# PIC18F4520_2.net
KiCad netlist of a schematic drawn in EAGLE
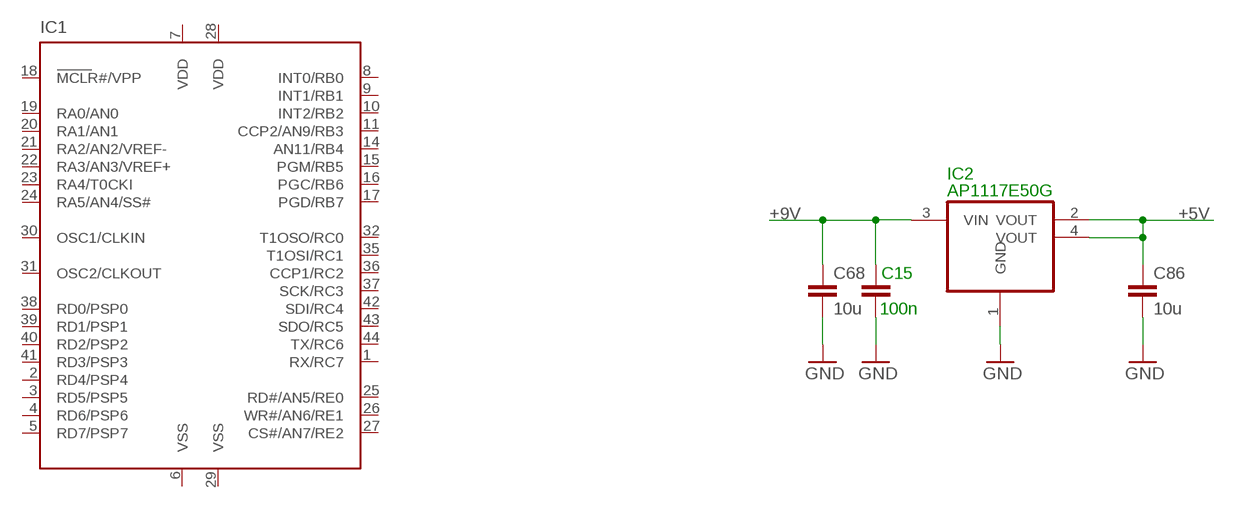
[diagram p0: schematic, sheet 1]

(export (version "E")
  (design (tool "Eeschema 10.0.6"))
  (components
    (comp (ref "C15")
      (value "100n")
      (footprint "eagle-import:C0805")
      (libsource (lib "eagle-import") (part "rcl_416_C-EUC0805"))
    )
    (comp (ref "C68")
      (value "10u")
      (footprint "eagle-import:C0805")
      (libsource (lib "eagle-import") (part "C-EUC0805"))
    )
    (comp (ref "C86")
      (value "10u")
      (footprint "eagle-import:C0805")
      (libsource (lib "eagle-import") (part "C-EUC0805"))
    )
    (comp (ref "IC1")
      (value "PIC18F4520")
      (footprint "eagle-import:TQFP44")
      (libsource (lib "eagle-import") (part "PIC18F4520"))
    )
    (comp (ref "IC2")
      (value "AP1117E50G")
      (footprint "eagle-import:SOT223")
      (libsource (lib "eagle-import") (part "REG1117-2OUT"))
    )
  )
  (nets
    (net (code "1") (name "/+5V") (class "Default")
      (node (ref "C86") (pin "1") (pinfunction "1_1") (pintype "passive"))
      (node (ref "IC2") (pin "2") (pinfunction "VOUT_2") (pintype "output"))
      (node (ref "IC2") (pin "4") (pinfunction "VOUT_4") (pintype "bidirectional"))
    )
    (net (code "2") (name "/+9V") (class "Default")
      (node (ref "C15") (pin "1") (pinfunction "1_1") (pintype "passive"))
      (node (ref "C68") (pin "1") (pinfunction "1_1") (pintype "passive"))
      (node (ref "IC2") (pin "3") (pinfunction "VIN_3") (pintype "input"))
    )
    (net (code "3") (name "GND") (class "Default")
      (node (ref "C15") (pin "2") (pinfunction "2_2") (pintype "passive"))
      (node (ref "C68") (pin "2") (pinfunction "2_2") (pintype "passive"))
      (node (ref "C86") (pin "2") (pinfunction "2_2") (pintype "passive"))
      (node (ref "IC2") (pin "1") (pinfunction "GND_1") (pintype "power_in"))
    )
    (net (code "4") (name "unconnected-(IC1-AN11{slash}RB4-Pad14)") (class "Default")
      (node (ref "IC1") (pin "14") (pinfunction "AN11/RB4_14") (pintype "bidirectional"))
    )
    (net (code "5") (name "unconnected-(IC1-CCP1{slash}RC2-Pad36)") (class "Default")
      (node (ref "IC1") (pin "36") (pinfunction "CCP1/RC2_36") (pintype "bidirectional"))
    )
    (net (code "6") (name "unconnected-(IC1-CCP2{slash}AN9{slash}RB3-Pad11)") (class "Default")
      (node (ref "IC1") (pin "11") (pinfunction "CCP2/AN9/RB3_11") (pintype "bidirectional"))
    )
    (net (code "7") (name "unconnected-(IC1-CS#{slash}AN7{slash}RE2-Pad27)") (class "Default")
      (node (ref "IC1") (pin "27") (pinfunction "CS#/AN7/RE2_27") (pintype "bidirectional"))
    )
    (net (code "8") (name "unconnected-(IC1-INT0{slash}RB0-Pad8)") (class "Default")
      (node (ref "IC1") (pin "8") (pinfunction "INT0/RB0_8") (pintype "bidirectional"))
    )
    (net (code "9") (name "unconnected-(IC1-INT1{slash}RB1-Pad9)") (class "Default")
      (node (ref "IC1") (pin "9") (pinfunction "INT1/RB1_9") (pintype "bidirectional"))
    )
    (net (code "10") (name "unconnected-(IC1-INT2{slash}RB2-Pad10)") (class "Default")
      (node (ref "IC1") (pin "10") (pinfunction "INT2/RB2_10") (pintype "bidirectional"))
    )
    (net (code "11") (name "unconnected-(IC1-MCLR#{slash}VPP-Pad18)") (class "Default")
      (node (ref "IC1") (pin "18") (pinfunction "MCLR#/VPP_18") (pintype "input"))
    )
    (net (code "12") (name "unconnected-(IC1-OSC1{slash}CLKIN-Pad30)") (class "Default")
      (node (ref "IC1") (pin "30") (pinfunction "OSC1/CLKIN_30") (pintype "input"))
    )
    (net (code "13") (name "unconnected-(IC1-OSC2{slash}CLKOUT-Pad31)") (class "Default")
      (node (ref "IC1") (pin "31") (pinfunction "OSC2/CLKOUT_31") (pintype "output"))
    )
    (net (code "14") (name "unconnected-(IC1-PGC{slash}RB6-Pad16)") (class "Default")
      (node (ref "IC1") (pin "16") (pinfunction "PGC/RB6_16") (pintype "bidirectional"))
    )
    (net (code "15") (name "unconnected-(IC1-PGD{slash}RB7-Pad17)") (class "Default")
      (node (ref "IC1") (pin "17") (pinfunction "PGD/RB7_17") (pintype "bidirectional"))
    )
    (net (code "16") (name "unconnected-(IC1-PGM{slash}RB5-Pad15)") (class "Default")
      (node (ref "IC1") (pin "15") (pinfunction "PGM/RB5_15") (pintype "bidirectional"))
    )
    (net (code "17") (name "unconnected-(IC1-RA0{slash}AN0-Pad19)") (class "Default")
      (node (ref "IC1") (pin "19") (pinfunction "RA0/AN0_19") (pintype "bidirectional"))
    )
    (net (code "18") (name "unconnected-(IC1-RA1{slash}AN1-Pad20)") (class "Default")
      (node (ref "IC1") (pin "20") (pinfunction "RA1/AN1_20") (pintype "bidirectional"))
    )
    (net (code "19") (name "unconnected-(IC1-RA2{slash}AN2{slash}VREF--Pad21)") (class "Default")
      (node (ref "IC1") (pin "21") (pinfunction "RA2/AN2/VREF-_21") (pintype "bidirectional"))
    )
    (net (code "20") (name "unconnected-(IC1-RA3{slash}AN3{slash}VREF+-Pad22)") (class "Default")
      (node (ref "IC1") (pin "22") (pinfunction "RA3/AN3/VREF+_22") (pintype "bidirectional"))
    )
    (net (code "21") (name "unconnected-(IC1-RA4{slash}T0CKI-Pad23)") (class "Default")
      (node (ref "IC1") (pin "23") (pinfunction "RA4/T0CKI_23") (pintype "bidirectional"))
    )
    (net (code "22") (name "unconnected-(IC1-RA5{slash}AN4{slash}SS#-Pad24)") (class "Default")
      (node (ref "IC1") (pin "24") (pinfunction "RA5/AN4/SS#_24") (pintype "bidirectional"))
    )
    (net (code "23") (name "unconnected-(IC1-RD#{slash}AN5{slash}RE0-Pad25)") (class "Default")
      (node (ref "IC1") (pin "25") (pinfunction "RD#/AN5/RE0_25") (pintype "bidirectional"))
    )
    (net (code "24") (name "unconnected-(IC1-RD0{slash}PSP0-Pad38)") (class "Default")
      (node (ref "IC1") (pin "38") (pinfunction "RD0/PSP0_38") (pintype "bidirectional"))
    )
    (net (code "25") (name "unconnected-(IC1-RD1{slash}PSP1-Pad39)") (class "Default")
      (node (ref "IC1") (pin "39") (pinfunction "RD1/PSP1_39") (pintype "bidirectional"))
    )
    (net (code "26") (name "unconnected-(IC1-RD2{slash}PSP2-Pad40)") (class "Default")
      (node (ref "IC1") (pin "40") (pinfunction "RD2/PSP2_40") (pintype "bidirectional"))
    )
    (net (code "27") (name "unconnected-(IC1-RD3{slash}PSP3-Pad41)") (class "Default")
      (node (ref "IC1") (pin "41") (pinfunction "RD3/PSP3_41") (pintype "bidirectional"))
    )
    (net (code "28") (name "unconnected-(IC1-RD4{slash}PSP4-Pad2)") (class "Default")
      (node (ref "IC1") (pin "2") (pinfunction "RD4/PSP4_2") (pintype "bidirectional"))
    )
    (net (code "29") (name "unconnected-(IC1-RD5{slash}PSP5-Pad3)") (class "Default")
      (node (ref "IC1") (pin "3") (pinfunction "RD5/PSP5_3") (pintype "bidirectional"))
    )
    (net (code "30") (name "unconnected-(IC1-RD6{slash}PSP6-Pad4)") (class "Default")
      (node (ref "IC1") (pin "4") (pinfunction "RD6/PSP6_4") (pintype "bidirectional"))
    )
    (net (code "31") (name "unconnected-(IC1-RD7{slash}PSP7-Pad5)") (class "Default")
      (node (ref "IC1") (pin "5") (pinfunction "RD7/PSP7_5") (pintype "bidirectional"))
    )
    (net (code "32") (name "unconnected-(IC1-RX{slash}RC7-Pad1)") (class "Default")
      (node (ref "IC1") (pin "1") (pinfunction "RX/RC7_1") (pintype "bidirectional"))
    )
    (net (code "33") (name "unconnected-(IC1-SCK{slash}RC3-Pad37)") (class "Default")
      (node (ref "IC1") (pin "37") (pinfunction "SCK/RC3_37") (pintype "bidirectional"))
    )
    (net (code "34") (name "unconnected-(IC1-SDI{slash}RC4-Pad42)") (class "Default")
      (node (ref "IC1") (pin "42") (pinfunction "SDI/RC4_42") (pintype "bidirectional"))
    )
    (net (code "35") (name "unconnected-(IC1-SDO{slash}RC5-Pad43)") (class "Default")
      (node (ref "IC1") (pin "43") (pinfunction "SDO/RC5_43") (pintype "bidirectional"))
    )
    (net (code "36") (name "unconnected-(IC1-T1OSI{slash}RC1-Pad35)") (class "Default")
      (node (ref "IC1") (pin "35") (pinfunction "T1OSI/RC1_35") (pintype "bidirectional"))
    )
    (net (code "37") (name "unconnected-(IC1-T1OSO{slash}RC0-Pad32)") (class "Default")
      (node (ref "IC1") (pin "32") (pinfunction "T1OSO/RC0_32") (pintype "bidirectional"))
    )
    (net (code "38") (name "unconnected-(IC1-TX{slash}RC6-Pad44)") (class "Default")
      (node (ref "IC1") (pin "44") (pinfunction "TX/RC6_44") (pintype "bidirectional"))
    )
    (net (code "39") (name "unconnected-(IC1-VDD-Pad7)") (class "Default")
      (node (ref "IC1") (pin "7") (pinfunction "VDD_7") (pintype "bidirectional"))
    )
    (net (code "40") (name "unconnected-(IC1-VDD-Pad28)") (class "Default")
      (node (ref "IC1") (pin "28") (pinfunction "VDD_28") (pintype "bidirectional"))
    )
    (net (code "41") (name "unconnected-(IC1-VSS-Pad6)") (class "Default")
      (node (ref "IC1") (pin "6") (pinfunction "VSS_6") (pintype "bidirectional"))
    )
    (net (code "42") (name "unconnected-(IC1-VSS-Pad29)") (class "Default")
      (node (ref "IC1") (pin "29") (pinfunction "VSS_29") (pintype "bidirectional"))
    )
    (net (code "43") (name "unconnected-(IC1-WR#{slash}AN6{slash}RE1-Pad26)") (class "Default")
      (node (ref "IC1") (pin "26") (pinfunction "WR#/AN6/RE1_26") (pintype "bidirectional"))
    )
  )
)
